# DisplayPrint.net
KiCad netlist of a schematic drawn in Altium Designer
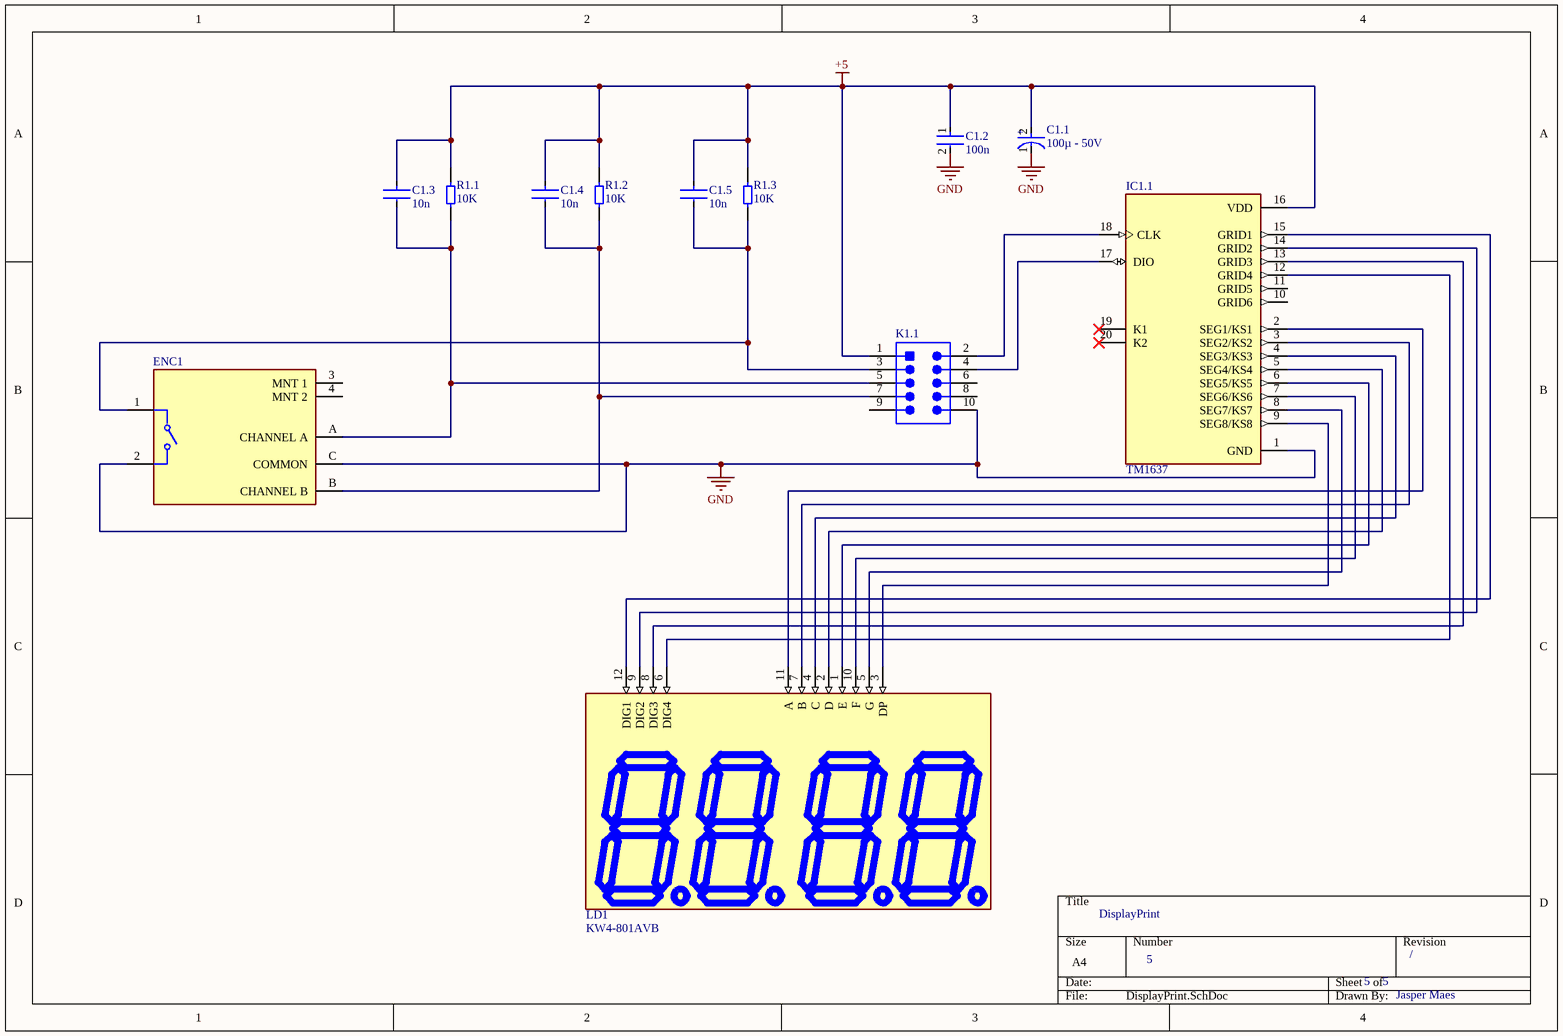
[diagram p0: DisplayPrint.SchDoc]

(export (version "E")
  (design (tool "Eeschema 10.0.6"))
  (components
    (comp (ref "C1.1")
      (value "100µ - 50V")
      (footprint "FP-RAD-TH-D_6_3_0_5-L_11-MFG")
      (description "Aluminum Electrolytic Capacitors (Radial Lead Type) 100uF ±20% 25V")
      (fields (field (name "TOLERANCE") "20%"))
      (libsource (lib "Soldeerstation") (part "CMP-05427-000897-1"))
    )
    (comp (ref "C1.2")
      (value "100n")
      (footprint "FP-C0805C-DN-IPC_A")
      (description "CAP CER 0.1UF 50V X7R 0805")
      (fields
        (field (name "MANUFACTURER PART NUMBER") "C0805C104K5RACTU")
        (field (name "MANUFACTURER") "KEMET")
      )
      (libsource (lib "") (part "CMP-2007-00279-2_1"))
    )
    (comp (ref "C1.3")
      (value "10n")
      (footprint "FP-C0805C-DN-IPC_A")
      (description "CAP CER 0.1UF 50V X7R 0805")
      (fields
        (field (name "MANUFACTURER PART NUMBER") "C0805C104K5RACTU")
        (field (name "MANUFACTURER") "KEMET")
      )
      (libsource (lib "Soldeerstation") (part "CMP-2007-00279-2"))
    )
    (comp (ref "C1.4")
      (value "10n")
      (footprint "FP-C0805C-DN-IPC_A")
      (description "CAP CER 0.1UF 50V X7R 0805")
      (fields
        (field (name "MANUFACTURER PART NUMBER") "C0805C104K5RACTU")
        (field (name "MANUFACTURER") "KEMET")
      )
      (libsource (lib "Soldeerstation") (part "CMP-2007-00279-2"))
    )
    (comp (ref "C1.5")
      (value "10n")
      (footprint "FP-C0805C-DN-IPC_A")
      (description "CAP CER 0.1UF 50V X7R 0805")
      (fields
        (field (name "MANUFACTURER PART NUMBER") "C0805C104K5RACTU")
        (field (name "MANUFACTURER") "KEMET")
      )
      (libsource (lib "Soldeerstation") (part "CMP-2007-00279-2"))
    )
    (comp (ref "ENC1")
      (value "PEC11R-4215F-S0024")
      (footprint "FP-PEC11R-4215F-S0024-MFG")
      (description "ROTARY ENCODER MECHANICAL 24PPR")
      (libsource (lib "Soldeerstation") (part "CMP-1747-00012-2"))
    )
    (comp (ref "IC1.1")
      (value "TM1637")
      (footprint "N14A")
      (description "LED Drive Control Special Circuit")
      (fields (field (name "MF") "Titan Micro Electronics"))
      (libsource (lib "Soldeerstation") (part "TM1637"))
    )
    (comp (ref "K1.1")
      (value "1-1634688-0")
      (footprint "TECO-1-1634688-0-10_V")
      (fields (field (name "MANUFACTURER") "TE Connectivity"))
      (libsource (lib "Soldeerstation") (part "CMP-2000-05854-1"))
    )
    (comp (ref "LD1")
      (value "KW4-801AVB")
      (footprint "LEDDIG_KW4-801AVB/KW4-801CVB_LUK")
      (description "Display, Seven Segment, 9.2MM, Red")
      (fields (field (name "MP") "LDQ-M3604RI") (field (name "MF") "Lumex"))
      (libsource (lib "Soldeerstation") (part "LDQ-M3604RI"))
    )
    (comp (ref "R1.1")
      (value "10K")
      (footprint "RESC2013X60X40ML20T25")
      (fields (field (name "PART NUMBER") "ERA6AEB332V") (field (name "MANUFACTURER") "Panasonic"))
      (libsource (lib "Soldeerstation") (part "CMP-2001-00629-1_1"))
    )
    (comp (ref "R1.2")
      (value "10K")
      (footprint "RESC2013X60X40ML20T25")
      (fields (field (name "PART NUMBER") "ERA6AEB332V") (field (name "MANUFACTURER") "Panasonic"))
      (libsource (lib "Soldeerstation") (part "CMP-2001-00629-1_1"))
    )
    (comp (ref "R1.3")
      (value "10K")
      (footprint "RESC2013X60X40ML20T25")
      (fields (field (name "PART NUMBER") "ERA6AEB332V") (field (name "MANUFACTURER") "Panasonic"))
      (libsource (lib "Soldeerstation") (part "CMP-2001-00629-1_1"))
    )
  )
  (nets
    (net (code "1") (name "+5") (class "Default")
      (node (ref "C1.1") (pin "2") (pinfunction "A_2") (pintype "passive"))
      (node (ref "C1.2") (pin "1") (pinfunction "1_1") (pintype "passive"))
      (node (ref "C1.3") (pin "1") (pinfunction "1_1") (pintype "passive"))
      (node (ref "C1.4") (pin "1") (pinfunction "1_1") (pintype "passive"))
      (node (ref "C1.5") (pin "1") (pinfunction "1_1") (pintype "passive"))
      (node (ref "IC1.1") (pin "16") (pinfunction "VDD_16") (pintype "power_in"))
      (node (ref "K1.1") (pin "1") (pinfunction "1_1") (pintype "passive"))
      (node (ref "R1.1") (pin "1") (pinfunction "1_1") (pintype "passive"))
      (node (ref "R1.2") (pin "1") (pinfunction "1_1") (pintype "passive"))
      (node (ref "R1.3") (pin "1") (pinfunction "1_1") (pintype "passive"))
    )
    (net (code "2") (name "GND") (class "Default")
      (node (ref "C1.1") (pin "1") (pinfunction "C_1") (pintype "passive"))
      (node (ref "C1.2") (pin "2") (pinfunction "2_2") (pintype "passive"))
      (node (ref "ENC1") (pin "2") (pinfunction "2_2") (pintype "passive"))
      (node (ref "ENC1") (pin "C") (pinfunction "COMMON_C") (pintype "passive"))
      (node (ref "IC1.1") (pin "1") (pinfunction "GND_1") (pintype "power_in"))
      (node (ref "K1.1") (pin "10") (pinfunction "10_10") (pintype "passive"))
    )
    (net (code "3") (name "Net-(C1.5-Pad2)") (class "Default")
      (node (ref "C1.5") (pin "2") (pinfunction "2_2") (pintype "passive"))
      (node (ref "ENC1") (pin "1") (pinfunction "1_1") (pintype "passive"))
      (node (ref "K1.1") (pin "3") (pinfunction "3_3") (pintype "passive"))
      (node (ref "R1.3") (pin "2") (pinfunction "2_2") (pintype "passive"))
    )
    (net (code "4") (name "Net-(ENC1-CHANNEL_A)") (class "Default")
      (node (ref "C1.3") (pin "2") (pinfunction "2_2") (pintype "passive"))
      (node (ref "ENC1") (pin "A") (pinfunction "CHANNEL_A_A") (pintype "passive"))
      (node (ref "K1.1") (pin "5") (pinfunction "5_5") (pintype "passive"))
      (node (ref "R1.1") (pin "2") (pinfunction "2_2") (pintype "passive"))
    )
    (net (code "5") (name "Net-(ENC1-CHANNEL_B)") (class "Default")
      (node (ref "C1.4") (pin "2") (pinfunction "2_2") (pintype "passive"))
      (node (ref "ENC1") (pin "B") (pinfunction "CHANNEL_B_B") (pintype "passive"))
      (node (ref "K1.1") (pin "7") (pinfunction "7_7") (pintype "passive"))
      (node (ref "R1.2") (pin "2") (pinfunction "2_2") (pintype "passive"))
    )
    (net (code "6") (name "Net-(IC1.1-CLK)") (class "Default")
      (node (ref "IC1.1") (pin "18") (pinfunction "CLK_18") (pintype "input"))
      (node (ref "K1.1") (pin "2") (pinfunction "2_2") (pintype "passive"))
    )
    (net (code "7") (name "Net-(IC1.1-DIO)") (class "Default")
      (node (ref "IC1.1") (pin "17") (pinfunction "DIO_17") (pintype "bidirectional"))
      (node (ref "K1.1") (pin "4") (pinfunction "4_4") (pintype "passive"))
    )
    (net (code "8") (name "Net-(IC1.1-GRID1)") (class "Default")
      (node (ref "IC1.1") (pin "15") (pinfunction "GRID1_15") (pintype "output"))
      (node (ref "LD1") (pin "12") (pinfunction "DIG1_12") (pintype "input"))
    )
    (net (code "9") (name "Net-(IC1.1-GRID2)") (class "Default")
      (node (ref "IC1.1") (pin "14") (pinfunction "GRID2_14") (pintype "output"))
      (node (ref "LD1") (pin "9") (pinfunction "DIG2_9") (pintype "input"))
    )
    (net (code "10") (name "Net-(IC1.1-GRID3)") (class "Default")
      (node (ref "IC1.1") (pin "13") (pinfunction "GRID3_13") (pintype "output"))
      (node (ref "LD1") (pin "8") (pinfunction "DIG3_8") (pintype "input"))
    )
    (net (code "11") (name "Net-(IC1.1-GRID4)") (class "Default")
      (node (ref "IC1.1") (pin "12") (pinfunction "GRID4_12") (pintype "output"))
      (node (ref "LD1") (pin "6") (pinfunction "DIG4_6") (pintype "input"))
    )
    (net (code "12") (name "Net-(IC1.1-SEG1{slash}KS1)") (class "Default")
      (node (ref "IC1.1") (pin "2") (pinfunction "SEG1/KS1_2") (pintype "output"))
      (node (ref "LD1") (pin "11") (pinfunction "A_11") (pintype "input"))
    )
    (net (code "13") (name "Net-(IC1.1-SEG2{slash}KS2)") (class "Default")
      (node (ref "IC1.1") (pin "3") (pinfunction "SEG2/KS2_3") (pintype "output"))
      (node (ref "LD1") (pin "7") (pinfunction "B_7") (pintype "input"))
    )
    (net (code "14") (name "Net-(IC1.1-SEG3{slash}KS3)") (class "Default")
      (node (ref "IC1.1") (pin "4") (pinfunction "SEG3/KS3_4") (pintype "output"))
      (node (ref "LD1") (pin "4") (pinfunction "C_4") (pintype "input"))
    )
    (net (code "15") (name "Net-(IC1.1-SEG4{slash}KS4)") (class "Default")
      (node (ref "IC1.1") (pin "5") (pinfunction "SEG4/KS4_5") (pintype "output"))
      (node (ref "LD1") (pin "2") (pinfunction "D_2") (pintype "input"))
    )
    (net (code "16") (name "Net-(IC1.1-SEG5{slash}KS5)") (class "Default")
      (node (ref "IC1.1") (pin "6") (pinfunction "SEG5/KS5_6") (pintype "output"))
      (node (ref "LD1") (pin "1") (pinfunction "E_1") (pintype "input"))
    )
    (net (code "17") (name "Net-(IC1.1-SEG6{slash}KS6)") (class "Default")
      (node (ref "IC1.1") (pin "7") (pinfunction "SEG6/KS6_7") (pintype "output"))
      (node (ref "LD1") (pin "10") (pinfunction "F_10") (pintype "input"))
    )
    (net (code "18") (name "Net-(IC1.1-SEG7{slash}KS7)") (class "Default")
      (node (ref "IC1.1") (pin "8") (pinfunction "SEG7/KS7_8") (pintype "output"))
      (node (ref "LD1") (pin "5") (pinfunction "G_5") (pintype "input"))
    )
    (net (code "19") (name "Net-(IC1.1-SEG8{slash}KS8)") (class "Default")
      (node (ref "IC1.1") (pin "9") (pinfunction "SEG8/KS8_9") (pintype "output"))
      (node (ref "LD1") (pin "3") (pinfunction "DP_3") (pintype "input"))
    )
    (net (code "20") (name "unconnected-(ENC1-MNT_1-Pad3)") (class "Default")
      (node (ref "ENC1") (pin "3") (pinfunction "MNT_1_3") (pintype "passive"))
    )
    (net (code "21") (name "unconnected-(ENC1-MNT_2-Pad4)") (class "Default")
      (node (ref "ENC1") (pin "4") (pinfunction "MNT_2_4") (pintype "passive"))
    )
    (net (code "22") (name "unconnected-(IC1.1-GRID5-Pad11)") (class "Default")
      (node (ref "IC1.1") (pin "11") (pinfunction "GRID5_11") (pintype "output"))
    )
    (net (code "23") (name "unconnected-(IC1.1-GRID6-Pad10)") (class "Default")
      (node (ref "IC1.1") (pin "10") (pinfunction "GRID6_10") (pintype "output"))
    )
    (net (code "24") (name "unconnected-(IC1.1-K1-Pad19)") (class "Default")
      (node (ref "IC1.1") (pin "19") (pinfunction "K1_19") (pintype "passive+no_connect"))
    )
    (net (code "25") (name "unconnected-(IC1.1-K2-Pad20)") (class "Default")
      (node (ref "IC1.1") (pin "20") (pinfunction "K2_20") (pintype "passive+no_connect"))
    )
    (net (code "26") (name "unconnected-(K1.1-Pad6)") (class "Default")
      (node (ref "K1.1") (pin "6") (pinfunction "6_6") (pintype "passive"))
    )
    (net (code "27") (name "unconnected-(K1.1-Pad8)") (class "Default")
      (node (ref "K1.1") (pin "8") (pinfunction "8_8") (pintype "passive"))
    )
    (net (code "28") (name "unconnected-(K1.1-Pad9)") (class "Default")
      (node (ref "K1.1") (pin "9") (pinfunction "9_9") (pintype "passive"))
    )
  )
)
